# RP2040_Evaluation_Connectors.net
KiCad netlist of a schematic drawn in Altium Designer
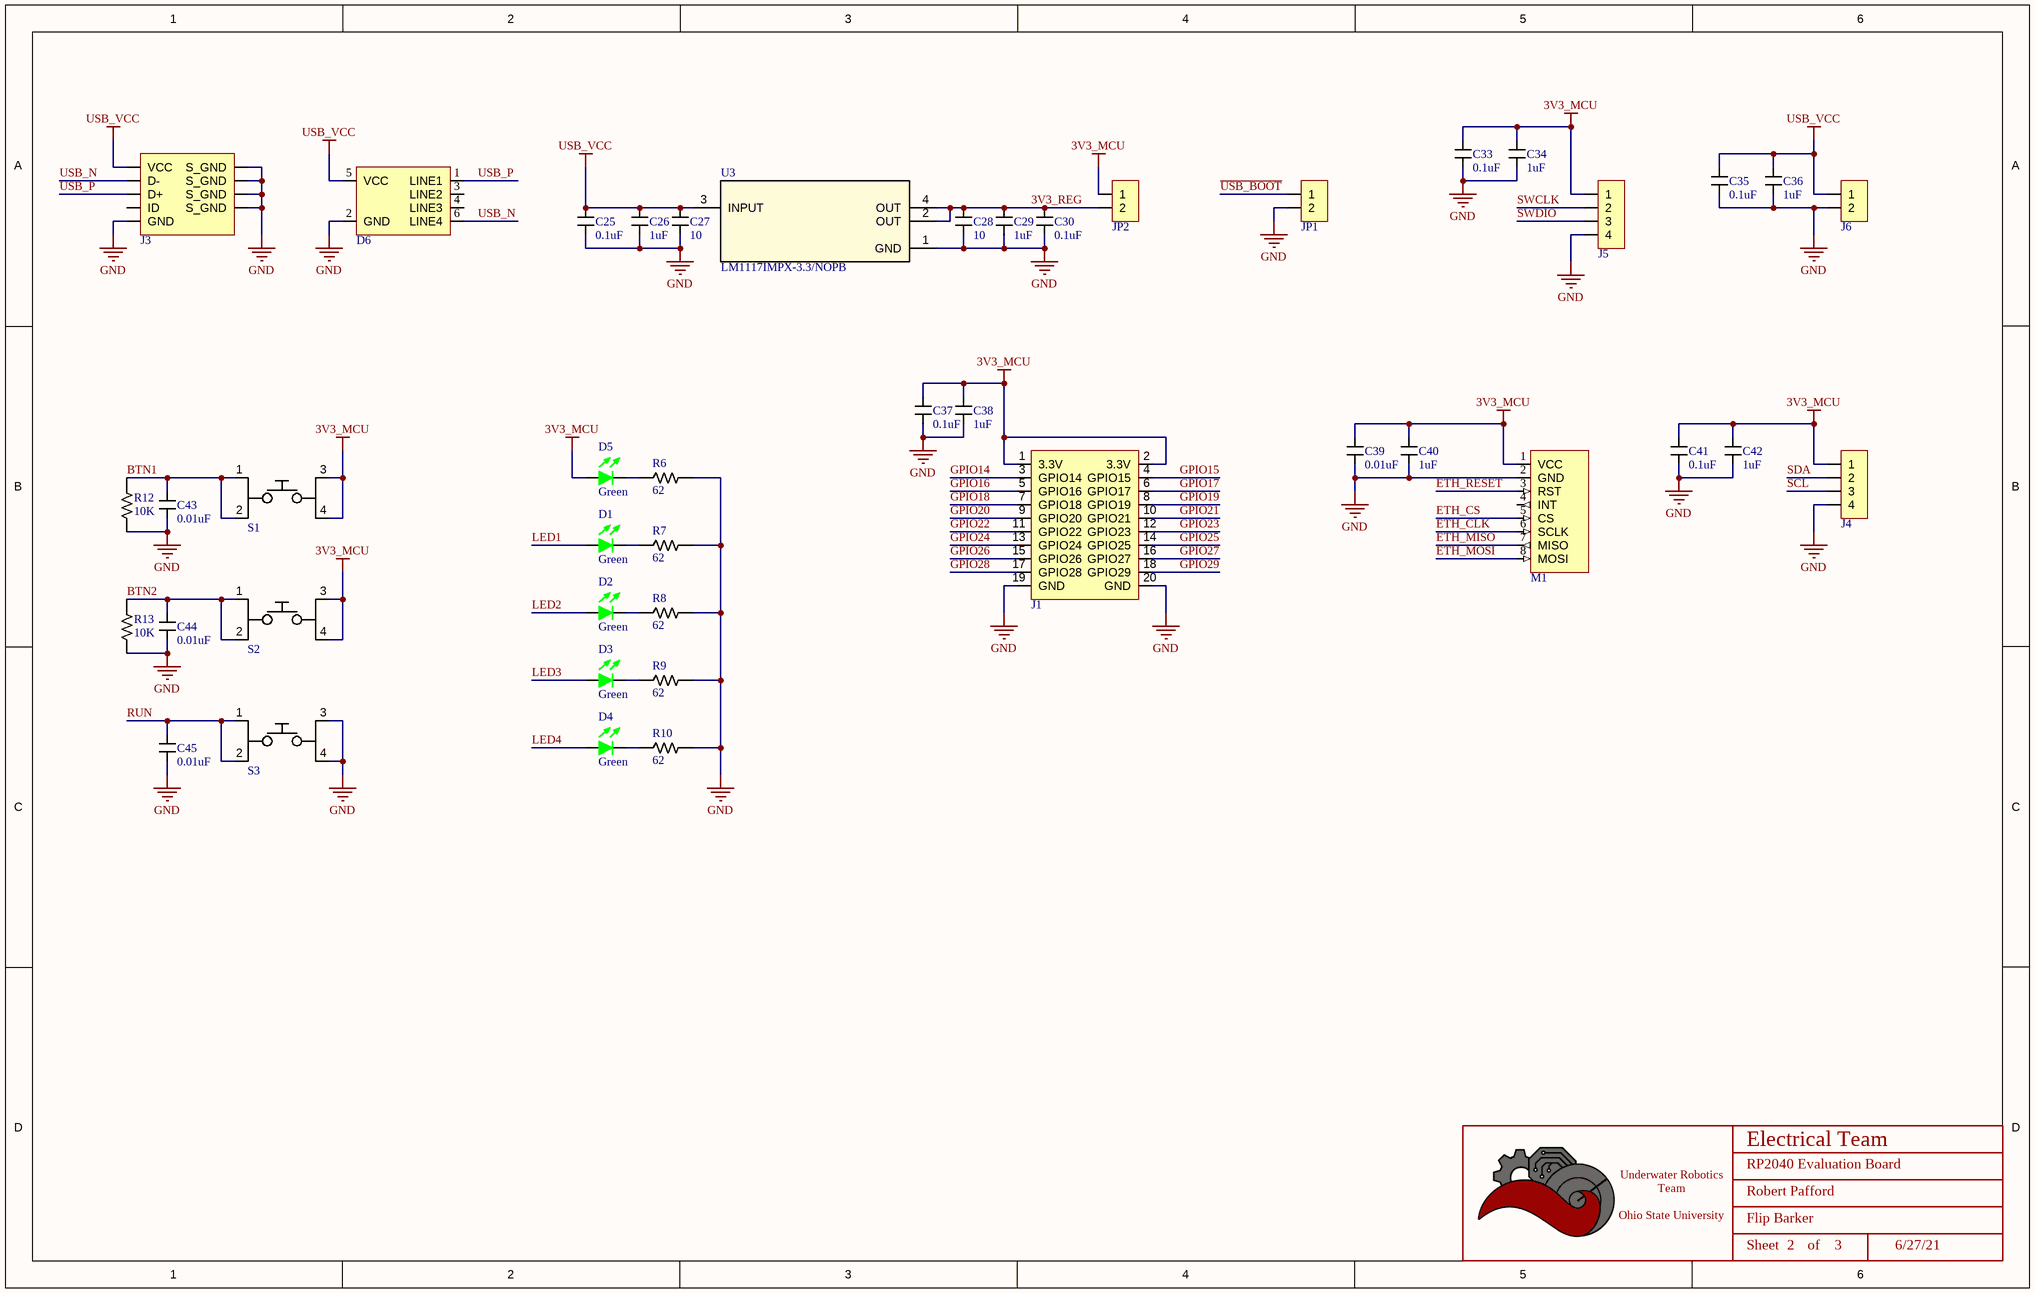
[diagram p0: RP2040_Evaluation_Connectors.SchDoc]

(export (version "E")
  (design (tool "Eeschema 10.0.6"))
  (components
    (comp (ref "C25")
      (value "0.1uF")
      (footprint "CAPACITOR_0603")
      (description "Cap 100nF 6.3V +/-10%\r\nCeramic 0603")
      (fields
        (field (name "TOLERANCE") "+/- 10%")
        (field (name "VOLTAGE") "6.3V")
        (field (name "MADE BY") "Flip B")
      )
      (libsource (lib "Capacitors") (part "CAPACITOR_0.1uF_0603"))
    )
    (comp (ref "C26")
      (value "1uF")
      (footprint "CAPACITOR_0603")
      (description "Cap 1uF 16V +/-10%\r\nCeramic 0603")
      (fields
        (field (name "TOLERANCE") "+/- 10%")
        (field (name "VOLTAGE") "16V")
        (field (name "MADE BY") "Flip B")
      )
      (libsource (lib "Capacitors") (part "CAPACITOR_1uF_0603"))
    )
    (comp (ref "C27")
      (value "10uF Ceramic 6.3V")
      (footprint "CAPACITOR_0603")
      (description "Cap 10uF 6.3V +/-20%\r\nCeramic 0603")
      (fields
        (field (name "TOLERANCE") "+/- 20%")
        (field (name "VOLTAGE") "6.3V")
        (field (name "VALUE (UF)") "10")
        (field (name "MADE BY") "Flip B")
      )
      (libsource (lib "Capacitors") (part "CAPACITOR_10uF_0603"))
    )
    (comp (ref "C28")
      (value "10uF Ceramic 6.3V")
      (footprint "CAPACITOR_0603")
      (description "Cap 10uF 6.3V +/-20%\r\nCeramic 0603")
      (fields
        (field (name "TOLERANCE") "+/- 20%")
        (field (name "VOLTAGE") "6.3V")
        (field (name "VALUE (UF)") "10")
        (field (name "MADE BY") "Flip B")
      )
      (libsource (lib "Capacitors") (part "CAPACITOR_10uF_0603"))
    )
    (comp (ref "C29")
      (value "1uF")
      (footprint "CAPACITOR_0603")
      (description "Cap 1uF 16V +/-10%\r\nCeramic 0603")
      (fields
        (field (name "TOLERANCE") "+/- 10%")
        (field (name "VOLTAGE") "16V")
        (field (name "MADE BY") "Flip B")
      )
      (libsource (lib "Capacitors") (part "CAPACITOR_1uF_0603"))
    )
    (comp (ref "C30")
      (value "0.1uF")
      (footprint "CAPACITOR_0603")
      (description "Cap 100nF 6.3V +/-10%\r\nCeramic 0603")
      (fields
        (field (name "TOLERANCE") "+/- 10%")
        (field (name "VOLTAGE") "6.3V")
        (field (name "MADE BY") "Flip B")
      )
      (libsource (lib "Capacitors") (part "CAPACITOR_0.1uF_0603"))
    )
    (comp (ref "C33")
      (value "0.1uF")
      (footprint "CAPACITOR_0603")
      (description "Cap 100nF 6.3V +/-10%\r\nCeramic 0603")
      (fields
        (field (name "TOLERANCE") "+/- 10%")
        (field (name "VOLTAGE") "6.3V")
        (field (name "MADE BY") "Flip B")
      )
      (libsource (lib "Capacitors") (part "CAPACITOR_0.1uF_0603"))
    )
    (comp (ref "C34")
      (value "1uF")
      (footprint "CAPACITOR_0603")
      (description "Cap 1uF 16V +/-10%\r\nCeramic 0603")
      (fields
        (field (name "TOLERANCE") "+/- 10%")
        (field (name "VOLTAGE") "16V")
        (field (name "MADE BY") "Flip B")
      )
      (libsource (lib "Capacitors") (part "CAPACITOR_1uF_0603"))
    )
    (comp (ref "C35")
      (value "0.1uF")
      (footprint "CAPACITOR_0603")
      (description "Cap 100nF 6.3V +/-10%\r\nCeramic 0603")
      (fields
        (field (name "TOLERANCE") "+/- 10%")
        (field (name "VOLTAGE") "6.3V")
        (field (name "MADE BY") "Flip B")
      )
      (libsource (lib "Capacitors") (part "CAPACITOR_0.1uF_0603"))
    )
    (comp (ref "C36")
      (value "1uF")
      (footprint "CAPACITOR_0603")
      (description "Cap 1uF 16V +/-10%\r\nCeramic 0603")
      (fields
        (field (name "TOLERANCE") "+/- 10%")
        (field (name "VOLTAGE") "16V")
        (field (name "MADE BY") "Flip B")
      )
      (libsource (lib "Capacitors") (part "CAPACITOR_1uF_0603"))
    )
    (comp (ref "C37")
      (value "0.1uF")
      (footprint "CAPACITOR_0603")
      (description "Cap 100nF 6.3V +/-10%\r\nCeramic 0603")
      (fields
        (field (name "TOLERANCE") "+/- 10%")
        (field (name "VOLTAGE") "6.3V")
        (field (name "MADE BY") "Flip B")
      )
      (libsource (lib "Capacitors") (part "CAPACITOR_0.1uF_0603"))
    )
    (comp (ref "C38")
      (value "1uF")
      (footprint "CAPACITOR_0603")
      (description "Cap 1uF 16V +/-10%\r\nCeramic 0603")
      (fields
        (field (name "TOLERANCE") "+/- 10%")
        (field (name "VOLTAGE") "16V")
        (field (name "MADE BY") "Flip B")
      )
      (libsource (lib "Capacitors") (part "CAPACITOR_1uF_0603"))
    )
    (comp (ref "C39")
      (value "0.01uF")
      (footprint "CAPACITOR_0603")
      (description "Cap 10nF 6.3V +/-20%\r\nCeramic 0603")
      (fields
        (field (name "TOLERANCE") "+/- 10%")
        (field (name "VOLTAGE") "6.3V")
        (field (name "MADE BY") "Flip B")
      )
      (libsource (lib "Capacitors") (part "CAPACITOR_0.01uF_0603"))
    )
    (comp (ref "C40")
      (value "1uF")
      (footprint "CAPACITOR_0603")
      (description "Cap 1uF 16V +/-10%\r\nCeramic 0603")
      (fields
        (field (name "TOLERANCE") "+/- 10%")
        (field (name "VOLTAGE") "16V")
        (field (name "MADE BY") "Flip B")
      )
      (libsource (lib "Capacitors") (part "CAPACITOR_1uF_0603"))
    )
    (comp (ref "C41")
      (value "0.1uF")
      (footprint "CAPACITOR_0603")
      (description "Cap 100nF 6.3V +/-10%\r\nCeramic 0603")
      (fields
        (field (name "TOLERANCE") "+/- 10%")
        (field (name "VOLTAGE") "6.3V")
        (field (name "MADE BY") "Flip B")
      )
      (libsource (lib "Capacitors") (part "CAPACITOR_0.1uF_0603"))
    )
    (comp (ref "C42")
      (value "1uF")
      (footprint "CAPACITOR_0603")
      (description "Cap 1uF 16V +/-10%\r\nCeramic 0603")
      (fields
        (field (name "TOLERANCE") "+/- 10%")
        (field (name "VOLTAGE") "16V")
        (field (name "MADE BY") "Flip B")
      )
      (libsource (lib "Capacitors") (part "CAPACITOR_1uF_0603"))
    )
    (comp (ref "C43")
      (value "0.01uF")
      (footprint "CAPACITOR_0603")
      (description "Cap 10nF 6.3V +/-20%\r\nCeramic 0603")
      (fields
        (field (name "TOLERANCE") "+/- 10%")
        (field (name "VOLTAGE") "6.3V")
        (field (name "MADE BY") "Flip B")
      )
      (libsource (lib "Capacitors") (part "CAPACITOR_0.01uF_0603"))
    )
    (comp (ref "C44")
      (value "0.01uF")
      (footprint "CAPACITOR_0603")
      (description "Cap 10nF 6.3V +/-20%\r\nCeramic 0603")
      (fields
        (field (name "TOLERANCE") "+/- 10%")
        (field (name "VOLTAGE") "6.3V")
        (field (name "MADE BY") "Flip B")
      )
      (libsource (lib "Capacitors") (part "CAPACITOR_0.01uF_0603"))
    )
    (comp (ref "C45")
      (value "0.01uF")
      (footprint "CAPACITOR_0603")
      (description "Cap 10nF 6.3V +/-20%\r\nCeramic 0603")
      (fields
        (field (name "TOLERANCE") "+/- 10%")
        (field (name "VOLTAGE") "6.3V")
        (field (name "MADE BY") "Flip B")
      )
      (libsource (lib "Capacitors") (part "CAPACITOR_0.01uF_0603"))
    )
    (comp (ref "D1")
      (value "IN-S63AT5G")
      (footprint "LED_0603")
      (description "LED Green Vf= 3V If = 0.005A\r\nIN-S63AT5G")
      (fields (field (name "COLOR") "Green") (field (name "MADE BY") "Robert Pafford"))
      (libsource (lib "Diodes") (part "LED_Green_0603_3V"))
    )
    (comp (ref "D2")
      (value "IN-S63AT5G")
      (footprint "LED_0603")
      (description "LED Green Vf= 3V If = 0.005A\r\nIN-S63AT5G")
      (fields (field (name "COLOR") "Green") (field (name "MADE BY") "Robert Pafford"))
      (libsource (lib "Diodes") (part "LED_Green_0603_3V"))
    )
    (comp (ref "D3")
      (value "IN-S63AT5G")
      (footprint "LED_0603")
      (description "LED Green Vf= 3V If = 0.005A\r\nIN-S63AT5G")
      (fields (field (name "COLOR") "Green") (field (name "MADE BY") "Robert Pafford"))
      (libsource (lib "Diodes") (part "LED_Green_0603_3V"))
    )
    (comp (ref "D4")
      (value "IN-S63AT5G")
      (footprint "LED_0603")
      (description "LED Green Vf= 3V If = 0.005A\r\nIN-S63AT5G")
      (fields (field (name "COLOR") "Green") (field (name "MADE BY") "Robert Pafford"))
      (libsource (lib "Diodes") (part "LED_Green_0603_3V"))
    )
    (comp (ref "D5")
      (value "IN-S63AT5G")
      (footprint "LED_0603")
      (description "LED Green Vf= 3V If = 0.005A\r\nIN-S63AT5G")
      (fields (field (name "COLOR") "Green") (field (name "MADE BY") "Robert Pafford"))
      (libsource (lib "Diodes") (part "LED_Green_0603_3V"))
    )
    (comp (ref "D6")
      (value "TVS DIODE 5VWM 25VC SOT23-6")
      (footprint "SOT 23-6L")
      (description "25V Clamp 6A (8/20µs) Ipp Tvs Diode Surface Mount SOT-23-6")
      (fields (field (name "MADE BY") "Robert Pafford"))
      (libsource (lib "Diodes") (part "RCLAMP0504S.TCT"))
    )
    (comp (ref "J1")
      (value "RP2040 GPIO Header")
      (footprint "HEADER_2x10PIN_2.54MM")
      (description "CONN HEADER VERT 20POS 2.54MM")
      (fields (field (name "MADE BY") "Robert Pafford"))
      (libsource (lib "Connectors") (part "HEADER_2x10PIN_2.54MM_RP2040_GPIO"))
    )
    (comp (ref "J3")
      (value "USB_MICRO R/A")
      (footprint "CONN_MINIUSB")
      (description "Amphenol Micro USB-B\r\nUSB2.0 5 Pin Right Angle SMD")
      (fields (field (name "MANUFACTURER") "Amphenol") (field (name "CREATED BY") "Flip B"))
      (libsource (lib "Connectors") (part "CONN_MICROUSB"))
    )
    (comp (ref "J4")
      (value "CONN HEADER VERT 4POS 2.54MM")
      (footprint "HEADER_4PIN_2.54MM")
      (fields (field (name "MADE BY") "Robert Pafford"))
      (libsource (lib "Connectors") (part "HEADER_4PIN_2.54MM"))
    )
    (comp (ref "J5")
      (value "CONN HEADER VERT 4POS 2.54MM")
      (footprint "HEADER_4PIN_2.54MM")
      (fields (field (name "MADE BY") "Robert Pafford"))
      (libsource (lib "Connectors") (part "HEADER_4PIN_2.54MM"))
    )
    (comp (ref "J6")
      (value "2 POS")
      (footprint "HEADER_2PIN_2.54MM")
      (description "CONN HEADER VERT 2POS 2.54MM")
      (fields (field (name "CREATED BY") "Robert P"))
      (libsource (lib "Connectors") (part "HEADER_2PIN_2.54MM"))
    )
    (comp (ref "JP1")
      (value "2 POS")
      (footprint "HEADER_2PIN_2.54MM")
      (description "CONN HEADER VERT 2POS 2.54MM")
      (fields (field (name "CREATED BY") "Robert P"))
      (libsource (lib "Connectors") (part "HEADER_2PIN_2.54MM"))
    )
    (comp (ref "JP2")
      (value "2 POS")
      (footprint "HEADER_2PIN_2.54MM")
      (description "CONN HEADER VERT 2POS 2.54MM")
      (fields (field (name "CREATED BY") "Robert P"))
      (libsource (lib "Connectors") (part "HEADER_2PIN_2.54MM"))
    )
    (comp (ref "M1")
      (value "W5x00 Breakout Board")
      (footprint "W5500IO-P")
      (description "W5x00 Breakout Board (W5500IO-P Compatible boards)")
      (fields (field (name "VOLTAGE") "3.3V") (field (name "MADE BY") "Robert Pafford"))
      (libsource (lib "Modules") (part "W5500IO-P"))
    )
    (comp (ref "R6")
      (value "62 Ohm 1% 1/4W")
      (footprint "RESISTOR_0603")
      (description "RES SMD 62 OHM 1% 1/4W 0603")
      (fields
        (field (name "TOLERANCE") "+/- 1%")
        (field (name "VALUE  (OHMS)") "62")
        (field (name "MADE BY") "Robert Pafford")
      )
      (libsource (lib "Resistors") (part "RESISTOR_62_0603"))
    )
    (comp (ref "R7")
      (value "62 Ohm 1% 1/4W")
      (footprint "RESISTOR_0603")
      (description "RES SMD 62 OHM 1% 1/4W 0603")
      (fields
        (field (name "TOLERANCE") "+/- 1%")
        (field (name "VALUE  (OHMS)") "62")
        (field (name "MADE BY") "Robert Pafford")
      )
      (libsource (lib "Resistors") (part "RESISTOR_62_0603"))
    )
    (comp (ref "R8")
      (value "62 Ohm 1% 1/4W")
      (footprint "RESISTOR_0603")
      (description "RES SMD 62 OHM 1% 1/4W 0603")
      (fields
        (field (name "TOLERANCE") "+/- 1%")
        (field (name "VALUE  (OHMS)") "62")
        (field (name "MADE BY") "Robert Pafford")
      )
      (libsource (lib "Resistors") (part "RESISTOR_62_0603"))
    )
    (comp (ref "R9")
      (value "62 Ohm 1% 1/4W")
      (footprint "RESISTOR_0603")
      (description "RES SMD 62 OHM 1% 1/4W 0603")
      (fields
        (field (name "TOLERANCE") "+/- 1%")
        (field (name "VALUE  (OHMS)") "62")
        (field (name "MADE BY") "Robert Pafford")
      )
      (libsource (lib "Resistors") (part "RESISTOR_62_0603"))
    )
    (comp (ref "R10")
      (value "62 Ohm 1% 1/4W")
      (footprint "RESISTOR_0603")
      (description "RES SMD 62 OHM 1% 1/4W 0603")
      (fields
        (field (name "TOLERANCE") "+/- 1%")
        (field (name "VALUE  (OHMS)") "62")
        (field (name "MADE BY") "Robert Pafford")
      )
      (libsource (lib "Resistors") (part "RESISTOR_62_0603"))
    )
    (comp (ref "R12")
      (value "10k Ohm 5% 1/10W")
      (footprint "RESISTOR_0603")
      (description "RES 10k OHM 5% 1/10W 0603")
      (fields
        (field (name "TOLERANCE") "+/- 5%")
        (field (name "VALUE  (OHMS)") "10K")
        (field (name "MADE BY") "Robert Pafford")
      )
      (libsource (lib "Resistors") (part "RESISTOR_10K_0603"))
    )
    (comp (ref "R13")
      (value "10k Ohm 5% 1/10W")
      (footprint "RESISTOR_0603")
      (description "RES 10k OHM 5% 1/10W 0603")
      (fields
        (field (name "TOLERANCE") "+/- 5%")
        (field (name "VALUE  (OHMS)") "10K")
        (field (name "MADE BY") "Robert Pafford")
      )
      (libsource (lib "Resistors") (part "RESISTOR_10K_0603"))
    )
    (comp (ref "S1")
      (value "SPST Tactile Switch")
      (footprint "TactileSwitch")
      (description "SWITCH TACTILE SPST-NO 0.05A 12V")
      (fields (field (name "MADE BY") "Robert Pafford"))
      (libsource (lib "Switches") (part "Tactile Switch"))
    )
    (comp (ref "S2")
      (value "SPST Tactile Switch")
      (footprint "TactileSwitch")
      (description "SWITCH TACTILE SPST-NO 0.05A 12V")
      (fields (field (name "MADE BY") "Robert Pafford"))
      (libsource (lib "Switches") (part "Tactile Switch"))
    )
    (comp (ref "S3")
      (value "SPST Tactile Switch")
      (footprint "TactileSwitch")
      (description "SWITCH TACTILE SPST-NO 0.05A 12V")
      (fields (field (name "MADE BY") "Robert Pafford"))
      (libsource (lib "Switches") (part "Tactile Switch"))
    )
    (comp (ref "U3")
      (value "LM1117IMPX-3.3/NOPB")
      (footprint "SOT-223-4")
      (description "IC REG LIN 3.3V 800MA SOT223-4")
      (fields
        (field (name "PARTNUMBER") "LM1117IMP-3.3/NOPB")
        (field (name "MANUFACTURER") "Texas Instruments")
        (field (name "CREATED BY") "Dylan T")
      )
      (libsource (lib "Converter") (part "LM1117IMPX-3.3/NOPB"))
    )
  )
  (nets
    (net (code "1") (name "/3V3_REG") (class "Default")
      (node (ref "C28") (pin "1") (pinfunction "1_1") (pintype "passive"))
      (node (ref "C29") (pin "1") (pinfunction "1_1") (pintype "passive"))
      (node (ref "C30") (pin "1") (pinfunction "1_1") (pintype "passive"))
      (node (ref "JP2") (pin "2") (pinfunction "2_2") (pintype "passive"))
      (node (ref "U3") (pin "2") (pinfunction "OUT_2") (pintype "power_in"))
      (node (ref "U3") (pin "4") (pinfunction "OUT_4") (pintype "power_in"))
    )
    (net (code "2") (name "/BTN1") (class "Default")
      (node (ref "C43") (pin "1") (pinfunction "1_1") (pintype "passive"))
      (node (ref "R12") (pin "1") (pinfunction "1_1") (pintype "passive"))
      (node (ref "S1") (pin "1") (pinfunction "1_1") (pintype "passive"))
      (node (ref "S1") (pin "2") (pinfunction "2_2") (pintype "passive"))
    )
    (net (code "3") (name "/BTN2") (class "Default")
      (node (ref "C44") (pin "1") (pinfunction "1_1") (pintype "passive"))
      (node (ref "R13") (pin "1") (pinfunction "1_1") (pintype "passive"))
      (node (ref "S2") (pin "1") (pinfunction "1_1") (pintype "passive"))
      (node (ref "S2") (pin "2") (pinfunction "2_2") (pintype "passive"))
    )
    (net (code "4") (name "/ETH_CLK") (class "Default")
      (node (ref "M1") (pin "6") (pinfunction "SCLK_6") (pintype "input"))
    )
    (net (code "5") (name "/ETH_CS") (class "Default")
      (node (ref "M1") (pin "5") (pinfunction "CS_5") (pintype "input"))
    )
    (net (code "6") (name "/ETH_MISO") (class "Default")
      (node (ref "M1") (pin "7") (pinfunction "MISO_7") (pintype "output"))
    )
    (net (code "7") (name "/ETH_MOSI") (class "Default")
      (node (ref "M1") (pin "8") (pinfunction "MOSI_8") (pintype "input"))
    )
    (net (code "8") (name "/ETH_RESET") (class "Default")
      (node (ref "M1") (pin "3") (pinfunction "RST_3") (pintype "input"))
    )
    (net (code "9") (name "/GPIO14") (class "Default")
      (node (ref "J1") (pin "3") (pinfunction "GPIO14_3") (pintype "bidirectional"))
    )
    (net (code "10") (name "/GPIO15") (class "Default")
      (node (ref "J1") (pin "4") (pinfunction "GPIO15_4") (pintype "bidirectional"))
    )
    (net (code "11") (name "/GPIO16") (class "Default")
      (node (ref "J1") (pin "5") (pinfunction "GPIO16_5") (pintype "bidirectional"))
    )
    (net (code "12") (name "/GPIO17") (class "Default")
      (node (ref "J1") (pin "6") (pinfunction "GPIO17_6") (pintype "bidirectional"))
    )
    (net (code "13") (name "/GPIO18") (class "Default")
      (node (ref "J1") (pin "7") (pinfunction "GPIO18_7") (pintype "bidirectional"))
    )
    (net (code "14") (name "/GPIO19") (class "Default")
      (node (ref "J1") (pin "8") (pinfunction "GPIO19_8") (pintype "bidirectional"))
    )
    (net (code "15") (name "/GPIO20") (class "Default")
      (node (ref "J1") (pin "9") (pinfunction "GPIO20_9") (pintype "bidirectional"))
    )
    (net (code "16") (name "/GPIO21") (class "Default")
      (node (ref "J1") (pin "10") (pinfunction "GPIO21_10") (pintype "bidirectional"))
    )
    (net (code "17") (name "/GPIO22") (class "Default")
      (node (ref "J1") (pin "11") (pinfunction "GPIO22_11") (pintype "bidirectional"))
    )
    (net (code "18") (name "/GPIO23") (class "Default")
      (node (ref "J1") (pin "12") (pinfunction "GPIO23_12") (pintype "bidirectional"))
    )
    (net (code "19") (name "/GPIO24") (class "Default")
      (node (ref "J1") (pin "13") (pinfunction "GPIO24_13") (pintype "bidirectional"))
    )
    (net (code "20") (name "/GPIO25") (class "Default")
      (node (ref "J1") (pin "14") (pinfunction "GPIO25_14") (pintype "bidirectional"))
    )
    (net (code "21") (name "/GPIO26") (class "Default")
      (node (ref "J1") (pin "15") (pinfunction "GPIO26_15") (pintype "bidirectional"))
    )
    (net (code "22") (name "/GPIO27") (class "Default")
      (node (ref "J1") (pin "16") (pinfunction "GPIO27_16") (pintype "bidirectional"))
    )
    (net (code "23") (name "/GPIO28") (class "Default")
      (node (ref "J1") (pin "17") (pinfunction "GPIO28_17") (pintype "bidirectional"))
    )
    (net (code "24") (name "/GPIO29") (class "Default")
      (node (ref "J1") (pin "18") (pinfunction "GPIO29_18") (pintype "bidirectional"))
    )
    (net (code "25") (name "/LED1") (class "Default")
      (node (ref "D1") (pin "1") (pinfunction "1_1") (pintype "passive"))
    )
    (net (code "26") (name "/LED2") (class "Default")
      (node (ref "D2") (pin "1") (pinfunction "1_1") (pintype "passive"))
    )
    (net (code "27") (name "/LED3") (class "Default")
      (node (ref "D3") (pin "1") (pinfunction "1_1") (pintype "passive"))
    )
    (net (code "28") (name "/LED4") (class "Default")
      (node (ref "D4") (pin "1") (pinfunction "1_1") (pintype "passive"))
    )
    (net (code "29") (name "/RUN") (class "Default")
      (node (ref "C45") (pin "1") (pinfunction "1_1") (pintype "passive"))
      (node (ref "S3") (pin "1") (pinfunction "1_1") (pintype "passive"))
      (node (ref "S3") (pin "2") (pinfunction "2_2") (pintype "passive"))
    )
    (net (code "30") (name "/SCL") (class "Default")
      (node (ref "J4") (pin "3") (pinfunction "3_3") (pintype "passive"))
    )
    (net (code "31") (name "/SDA") (class "Default")
      (node (ref "J4") (pin "2") (pinfunction "2_2") (pintype "passive"))
    )
    (net (code "32") (name "/SWCLK") (class "Default")
      (node (ref "J5") (pin "2") (pinfunction "2_2") (pintype "passive"))
    )
    (net (code "33") (name "/SWDIO") (class "Default")
      (node (ref "J5") (pin "3") (pinfunction "3_3") (pintype "passive"))
    )
    (net (code "34") (name "/USB_N") (class "Default")
      (node (ref "D6") (pin "6") (pinfunction "LINE4_6") (pintype "passive"))
      (node (ref "J3") (pin "2") (pinfunction "D-_2") (pintype "passive"))
    )
    (net (code "35") (name "/USB_P") (class "Default")
      (node (ref "D6") (pin "1") (pinfunction "LINE1_1") (pintype "passive"))
      (node (ref "J3") (pin "3") (pinfunction "D+_3") (pintype "passive"))
    )
    (net (code "36") (name "/~{USB_BOOT}") (class "Default")
      (node (ref "JP1") (pin "1") (pinfunction "1_1") (pintype "passive"))
    )
    (net (code "37") (name "3V3_MCU") (class "Default")
      (node (ref "C33") (pin "1") (pinfunction "1_1") (pintype "passive"))
      (node (ref "C34") (pin "1") (pinfunction "1_1") (pintype "passive"))
      (node (ref "C37") (pin "1") (pinfunction "1_1") (pintype "passive"))
      (node (ref "C38") (pin "1") (pinfunction "1_1") (pintype "passive"))
      (node (ref "C39") (pin "1") (pinfunction "1_1") (pintype "passive"))
      (node (ref "C40") (pin "1") (pinfunction "1_1") (pintype "passive"))
      (node (ref "C41") (pin "1") (pinfunction "1_1") (pintype "passive"))
      (node (ref "C42") (pin "1") (pinfunction "1_1") (pintype "passive"))
      (node (ref "D5") (pin "1") (pinfunction "1_1") (pintype "passive"))
      (node (ref "J1") (pin "1") (pinfunction "3.3V_1") (pintype "power_in"))
      (node (ref "J1") (pin "2") (pinfunction "3.3V_2") (pintype "power_in"))
      (node (ref "J4") (pin "1") (pinfunction "1_1") (pintype "passive"))
      (node (ref "J5") (pin "1") (pinfunction "1_1") (pintype "passive"))
      (node (ref "JP2") (pin "1") (pinfunction "1_1") (pintype "passive"))
      (node (ref "M1") (pin "1") (pinfunction "VCC_1") (pintype "power_in"))
      (node (ref "S1") (pin "3") (pinfunction "3_3") (pintype "passive"))
      (node (ref "S1") (pin "4") (pinfunction "4_4") (pintype "passive"))
      (node (ref "S2") (pin "3") (pinfunction "3_3") (pintype "passive"))
      (node (ref "S2") (pin "4") (pinfunction "4_4") (pintype "passive"))
    )
    (net (code "38") (name "GND") (class "Default")
      (node (ref "C25") (pin "2") (pinfunction "2_2") (pintype "passive"))
      (node (ref "C26") (pin "2") (pinfunction "2_2") (pintype "passive"))
      (node (ref "C27") (pin "2") (pinfunction "2_2") (pintype "passive"))
      (node (ref "C28") (pin "2") (pinfunction "2_2") (pintype "passive"))
      (node (ref "C29") (pin "2") (pinfunction "2_2") (pintype "passive"))
      (node (ref "C30") (pin "2") (pinfunction "2_2") (pintype "passive"))
      (node (ref "C33") (pin "2") (pinfunction "2_2") (pintype "passive"))
      (node (ref "C34") (pin "2") (pinfunction "2_2") (pintype "passive"))
      (node (ref "C35") (pin "2") (pinfunction "2_2") (pintype "passive"))
      (node (ref "C36") (pin "1") (pinfunction "1_1") (pintype "passive"))
      (node (ref "C37") (pin "2") (pinfunction "2_2") (pintype "passive"))
      (node (ref "C38") (pin "2") (pinfunction "2_2") (pintype "passive"))
      (node (ref "C39") (pin "2") (pinfunction "2_2") (pintype "passive"))
      (node (ref "C40") (pin "2") (pinfunction "2_2") (pintype "passive"))
      (node (ref "C41") (pin "2") (pinfunction "2_2") (pintype "passive"))
      (node (ref "C42") (pin "2") (pinfunction "2_2") (pintype "passive"))
      (node (ref "C43") (pin "2") (pinfunction "2_2") (pintype "passive"))
      (node (ref "C44") (pin "2") (pinfunction "2_2") (pintype "passive"))
      (node (ref "C45") (pin "2") (pinfunction "2_2") (pintype "passive"))
      (node (ref "D6") (pin "2") (pinfunction "GND_2") (pintype "power_in"))
      (node (ref "J1") (pin "19") (pinfunction "GND_19") (pintype "power_in"))
      (node (ref "J1") (pin "20") (pinfunction "GND_20") (pintype "power_in"))
      (node (ref "J3") (pin "5") (pinfunction "GND_5") (pintype "passive"))
      (node (ref "J3") (pin "6") (pinfunction "S_GND_6") (pintype "passive"))
      (node (ref "J3") (pin "7") (pinfunction "S_GND_7") (pintype "passive"))
      (node (ref "J3") (pin "8") (pinfunction "S_GND_8") (pintype "passive"))
      (node (ref "J3") (pin "9") (pinfunction "S_GND_9") (pintype "passive"))
      (node (ref "J4") (pin "4") (pinfunction "4_4") (pintype "passive"))
      (node (ref "J5") (pin "4") (pinfunction "4_4") (pintype "passive"))
      (node (ref "J6") (pin "2") (pinfunction "2_2") (pintype "passive"))
      (node (ref "JP1") (pin "2") (pinfunction "2_2") (pintype "passive"))
      (node (ref "M1") (pin "2") (pinfunction "GND_2") (pintype "power_in"))
      (node (ref "R10") (pin "1") (pinfunction "1_1") (pintype "passive"))
      (node (ref "R12") (pin "2") (pinfunction "2_2") (pintype "passive"))
      (node (ref "R13") (pin "2") (pinfunction "2_2") (pintype "passive"))
      (node (ref "R6") (pin "1") (pinfunction "1_1") (pintype "passive"))
      (node (ref "R7") (pin "1") (pinfunction "1_1") (pintype "passive"))
      (node (ref "R8") (pin "1") (pinfunction "1_1") (pintype "passive"))
      (node (ref "R9") (pin "1") (pinfunction "1_1") (pintype "passive"))
      (node (ref "S3") (pin "3") (pinfunction "3_3") (pintype "passive"))
      (node (ref "S3") (pin "4") (pinfunction "4_4") (pintype "passive"))
      (node (ref "U3") (pin "1") (pinfunction "GND_1") (pintype "power_in"))
    )
    (net (code "39") (name "Net-(D1-Pad2)") (class "Default")
      (node (ref "D1") (pin "2") (pinfunction "2_2") (pintype "passive"))
      (node (ref "R7") (pin "2") (pinfunction "2_2") (pintype "passive"))
    )
    (net (code "40") (name "Net-(D2-Pad2)") (class "Default")
      (node (ref "D2") (pin "2") (pinfunction "2_2") (pintype "passive"))
      (node (ref "R8") (pin "2") (pinfunction "2_2") (pintype "passive"))
    )
    (net (code "41") (name "Net-(D3-Pad2)") (class "Default")
      (node (ref "D3") (pin "2") (pinfunction "2_2") (pintype "passive"))
      (node (ref "R9") (pin "2") (pinfunction "2_2") (pintype "passive"))
    )
    (net (code "42") (name "Net-(D4-Pad2)") (class "Default")
      (node (ref "D4") (pin "2") (pinfunction "2_2") (pintype "passive"))
      (node (ref "R10") (pin "2") (pinfunction "2_2") (pintype "passive"))
    )
    (net (code "43") (name "Net-(D5-Pad2)") (class "Default")
      (node (ref "D5") (pin "2") (pinfunction "2_2") (pintype "passive"))
      (node (ref "R6") (pin "2") (pinfunction "2_2") (pintype "passive"))
    )
    (net (code "44") (name "USB_VCC") (class "Default")
      (node (ref "C25") (pin "1") (pinfunction "1_1") (pintype "passive"))
      (node (ref "C26") (pin "1") (pinfunction "1_1") (pintype "passive"))
      (node (ref "C27") (pin "1") (pinfunction "1_1") (pintype "passive"))
      (node (ref "C35") (pin "1") (pinfunction "1_1") (pintype "passive"))
      (node (ref "C36") (pin "2") (pinfunction "2_2") (pintype "passive"))
      (node (ref "D6") (pin "5") (pinfunction "VCC_5") (pintype "power_in"))
      (node (ref "J3") (pin "1") (pinfunction "VCC_1") (pintype "passive"))
      (node (ref "J6") (pin "1") (pinfunction "1_1") (pintype "passive"))
      (node (ref "U3") (pin "3") (pinfunction "INPUT_3") (pintype "power_in"))
    )
    (net (code "45") (name "unconnected-(D6-LINE2-Pad3)") (class "Default")
      (node (ref "D6") (pin "3") (pinfunction "LINE2_3") (pintype "passive"))
    )
    (net (code "46") (name "unconnected-(D6-LINE3-Pad4)") (class "Default")
      (node (ref "D6") (pin "4") (pinfunction "LINE3_4") (pintype "passive"))
    )
    (net (code "47") (name "unconnected-(J3-ID-Pad4)") (class "Default")
      (node (ref "J3") (pin "4") (pinfunction "ID_4") (pintype "passive"))
    )
    (net (code "48") (name "unconnected-(M1-INT-Pad4)") (class "Default")
      (node (ref "M1") (pin "4") (pinfunction "INT_4") (pintype "output"))
    )
  )
)
